# tvbgone.net
KiCad netlist of a schematic drawn in EAGLE
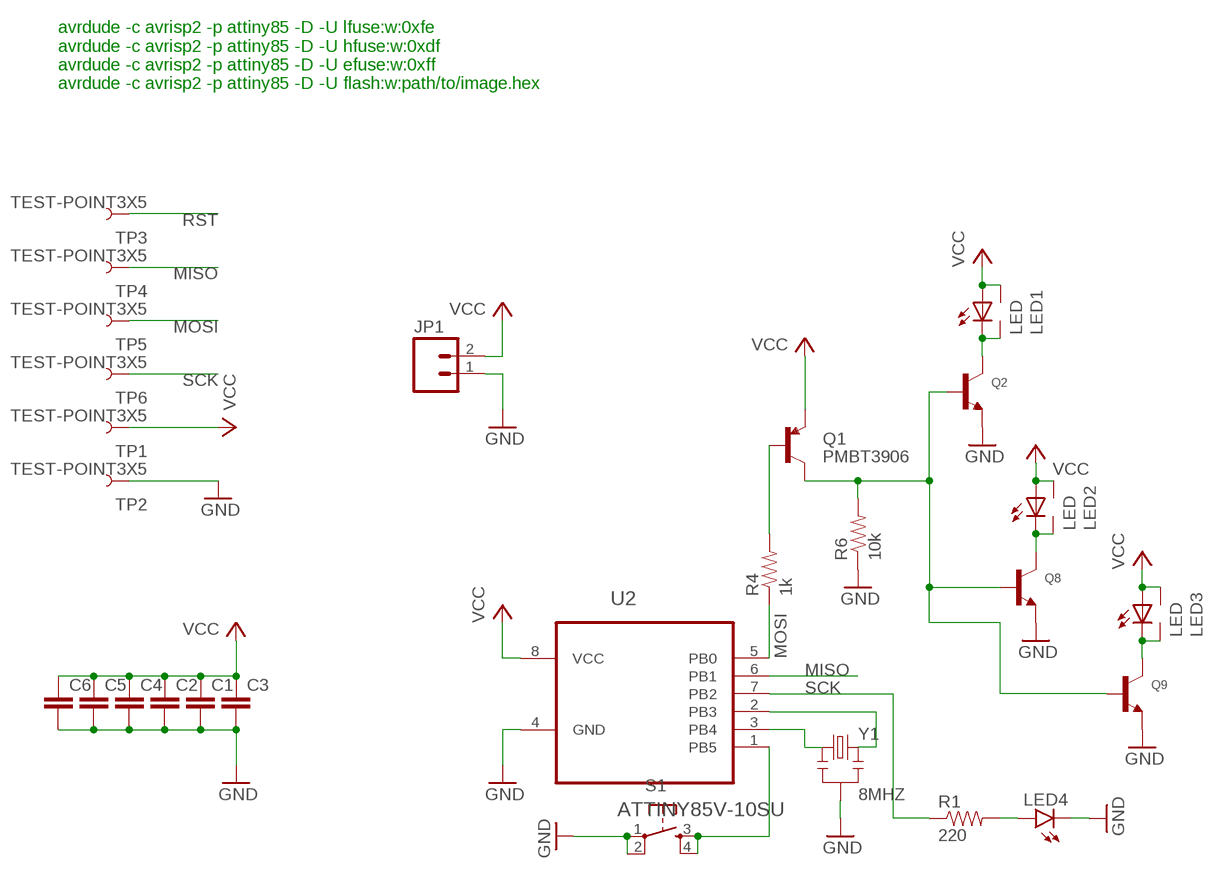
[diagram p0: schematic, sheet 1]

(export (version "E")
  (design (tool "Eeschema 10.0.6"))
  (components
    (comp (ref "C1")
      (value "CAP0603-CAP")
      (footprint "eagle-import:0603-CAP")
      (libsource (lib "eagle-import") (part "CAP0603-CAP"))
    )
    (comp (ref "C2")
      (value "CAP0603-CAP")
      (footprint "eagle-import:0603-CAP")
      (libsource (lib "eagle-import") (part "CAP0603-CAP"))
    )
    (comp (ref "C3")
      (value "CAP0603-CAP")
      (footprint "eagle-import:0603-CAP")
      (libsource (lib "eagle-import") (part "CAP0603-CAP"))
    )
    (comp (ref "C4")
      (value "CAP0603-CAP")
      (footprint "eagle-import:0603-CAP")
      (libsource (lib "eagle-import") (part "CAP0603-CAP"))
    )
    (comp (ref "C5")
      (value "CAP0603-CAP")
      (footprint "eagle-import:0603-CAP")
      (libsource (lib "eagle-import") (part "CAP0603-CAP"))
    )
    (comp (ref "C6")
      (value "CAP0603-CAP")
      (footprint "eagle-import:0603-CAP")
      (libsource (lib "eagle-import") (part "CAP0603-CAP"))
    )
    (comp (ref "JP1")
      (value "M02LOCK")
      (footprint "eagle-import:1X02_LOCK")
      (libsource (lib "eagle-import") (part "M02LOCK"))
    )
    (comp (ref "LED1")
      (value "LED")
      (footprint "eagle-import:5MM-SIDE")
      (libsource (lib "eagle-import") (part "LED"))
    )
    (comp (ref "LED2")
      (value "LED")
      (footprint "eagle-import:5MM-SIDE")
      (libsource (lib "eagle-import") (part "LED"))
    )
    (comp (ref "LED3")
      (value "LED")
      (footprint "eagle-import:5MM-SIDE")
      (libsource (lib "eagle-import") (part "LED"))
    )
    (comp (ref "LED4")
      (value "LED0603")
      (footprint "eagle-import:LED-0603")
      (libsource (lib "eagle-import") (part "LED0603"))
    )
    (comp (ref "Q1")
      (value "PMBT3906")
      (footprint "eagle-import:SOT23-3")
      (libsource (lib "eagle-import") (part "TRANSISTOR_PNPPMBT3906"))
    )
    (comp (ref "Q2")
      (value "TRANSISTOR_NPN")
      (footprint "eagle-import:SOT-23-R")
      (libsource (lib "eagle-import") (part "TRANSISTOR_NPN"))
    )
    (comp (ref "Q8")
      (value "TRANSISTOR_NPN")
      (footprint "eagle-import:SOT-23-R")
      (libsource (lib "eagle-import") (part "TRANSISTOR_NPN"))
    )
    (comp (ref "Q9")
      (value "TRANSISTOR_NPN")
      (footprint "eagle-import:SOT-23-R")
      (libsource (lib "eagle-import") (part "TRANSISTOR_NPN"))
    )
    (comp (ref "R1")
      (value "220")
      (footprint "eagle-import:0603-RES")
      (libsource (lib "eagle-import") (part "RESISTOR0603"))
    )
    (comp (ref "R4")
      (value "1k")
      (footprint "eagle-import:0603-RES")
      (libsource (lib "eagle-import") (part "RESISTOR0603"))
    )
    (comp (ref "R6")
      (value "10k")
      (footprint "eagle-import:0603-RES")
      (libsource (lib "eagle-import") (part "RESISTOR0603"))
    )
    (comp (ref "S1")
      (value "TAC_SWITCHSMD")
      (footprint "eagle-import:TACTILE-SWITCH-SMD")
      (libsource (lib "eagle-import") (part "TAC_SWITCHSMD"))
    )
    (comp (ref "TP1")
      (value "TEST-POINT3X5")
      (footprint "eagle-import:PAD.03X.05")
      (libsource (lib "eagle-import") (part "TEST-POINT3X5"))
    )
    (comp (ref "TP2")
      (value "TEST-POINT3X5")
      (footprint "eagle-import:PAD.03X.05")
      (libsource (lib "eagle-import") (part "TEST-POINT3X5"))
    )
    (comp (ref "TP3")
      (value "TEST-POINT3X5")
      (footprint "eagle-import:PAD.03X.05")
      (libsource (lib "eagle-import") (part "TEST-POINT3X5"))
    )
    (comp (ref "TP4")
      (value "TEST-POINT3X5")
      (footprint "eagle-import:PAD.03X.05")
      (libsource (lib "eagle-import") (part "TEST-POINT3X5"))
    )
    (comp (ref "TP5")
      (value "TEST-POINT3X5")
      (footprint "eagle-import:PAD.03X.05")
      (libsource (lib "eagle-import") (part "TEST-POINT3X5"))
    )
    (comp (ref "TP6")
      (value "TEST-POINT3X5")
      (footprint "eagle-import:PAD.03X.05")
      (libsource (lib "eagle-import") (part "TEST-POINT3X5"))
    )
    (comp (ref "U2")
      (value "ATTINY85V-10SU")
      (footprint "eagle-import:SOIC127P798X216-8N")
      (libsource (lib "eagle-import") (part "ATTINY85V-10SU"))
    )
    (comp (ref "Y1")
      (value "8MHZ")
      (footprint "eagle-import:RESONATOR-SMD")
      (libsource (lib "eagle-import") (part "RESONATOR8MHZ"))
    )
  )
  (nets
    (net (code "1") (name "/MISO") (class "Default")
      (node (ref "TP4") (pin "P$1") (pinfunction "1_P$1") (pintype "bidirectional"))
      (node (ref "U2") (pin "6") (pinfunction "PB1_6") (pintype "bidirectional"))
    )
    (net (code "2") (name "/MOSI") (class "Default")
      (node (ref "R4") (pin "1") (pinfunction "1_1") (pintype "passive"))
      (node (ref "TP5") (pin "P$1") (pinfunction "1_P$1") (pintype "bidirectional"))
      (node (ref "U2") (pin "5") (pinfunction "PB0_5") (pintype "bidirectional"))
    )
    (net (code "3") (name "/RST") (class "Default")
      (node (ref "S1") (pin "3") (pinfunction "3_3") (pintype "passive"))
      (node (ref "S1") (pin "4") (pinfunction "4_4") (pintype "passive"))
      (node (ref "TP3") (pin "P$1") (pinfunction "1_P$1") (pintype "bidirectional"))
      (node (ref "U2") (pin "1") (pinfunction "PB5_1") (pintype "bidirectional"))
    )
    (net (code "4") (name "/SCK") (class "Default")
      (node (ref "R1") (pin "1") (pinfunction "1_1") (pintype "passive"))
      (node (ref "TP6") (pin "P$1") (pinfunction "1_P$1") (pintype "bidirectional"))
      (node (ref "U2") (pin "7") (pinfunction "PB2_7") (pintype "bidirectional"))
    )
    (net (code "5") (name "GND") (class "Default")
      (node (ref "C1") (pin "2") (pinfunction "2_2") (pintype "passive"))
      (node (ref "C2") (pin "2") (pinfunction "2_2") (pintype "passive"))
      (node (ref "C3") (pin "2") (pinfunction "2_2") (pintype "passive"))
      (node (ref "C4") (pin "2") (pinfunction "2_2") (pintype "passive"))
      (node (ref "C5") (pin "2") (pinfunction "2_2") (pintype "passive"))
      (node (ref "C6") (pin "2") (pinfunction "2_2") (pintype "passive"))
      (node (ref "JP1") (pin "1") (pinfunction "1_1") (pintype "passive"))
      (node (ref "LED4") (pin "C") (pinfunction "C_C") (pintype "passive"))
      (node (ref "Q2") (pin "3-EMITTER") (pinfunction "E_3-EMITTER") (pintype "passive"))
      (node (ref "Q8") (pin "3-EMITTER") (pinfunction "E_3-EMITTER") (pintype "passive"))
      (node (ref "Q9") (pin "3-EMITTER") (pinfunction "E_3-EMITTER") (pintype "passive"))
      (node (ref "R6") (pin "1") (pinfunction "1_1") (pintype "passive"))
      (node (ref "S1") (pin "1") (pinfunction "1_1") (pintype "passive"))
      (node (ref "S1") (pin "2") (pinfunction "2_2") (pintype "passive"))
      (node (ref "TP2") (pin "P$1") (pinfunction "1_P$1") (pintype "bidirectional"))
      (node (ref "U2") (pin "4") (pinfunction "GND_4") (pintype "passive"))
      (node (ref "Y1") (pin "2") (pinfunction "2_2") (pintype "passive"))
    )
    (net (code "6") (name "Net-(LED1-C)") (class "Default")
      (node (ref "LED1") (pin "K") (pinfunction "C_K") (pintype "passive"))
      (node (ref "LED1") (pin "K2") (pinfunction "C1_K2") (pintype "passive"))
      (node (ref "Q2") (pin "2-COLLECTOR") (pinfunction "C_2-COLLECTOR") (pintype "passive"))
    )
    (net (code "7") (name "Net-(LED2-C)") (class "Default")
      (node (ref "LED2") (pin "K") (pinfunction "C_K") (pintype "passive"))
      (node (ref "LED2") (pin "K2") (pinfunction "C1_K2") (pintype "passive"))
      (node (ref "Q8") (pin "2-COLLECTOR") (pinfunction "C_2-COLLECTOR") (pintype "passive"))
    )
    (net (code "8") (name "Net-(LED3-C)") (class "Default")
      (node (ref "LED3") (pin "K") (pinfunction "C_K") (pintype "passive"))
      (node (ref "LED3") (pin "K2") (pinfunction "C1_K2") (pintype "passive"))
      (node (ref "Q9") (pin "2-COLLECTOR") (pinfunction "C_2-COLLECTOR") (pintype "passive"))
    )
    (net (code "9") (name "Net-(LED4-PadA)") (class "Default")
      (node (ref "LED4") (pin "A") (pinfunction "A_A") (pintype "passive"))
      (node (ref "R1") (pin "2") (pinfunction "2_2") (pintype "passive"))
    )
    (net (code "10") (name "Net-(Q1-B)") (class "Default")
      (node (ref "Q1") (pin "1") (pinfunction "B_1") (pintype "passive"))
      (node (ref "R4") (pin "2") (pinfunction "2_2") (pintype "passive"))
    )
    (net (code "11") (name "Net-(Q1-C)") (class "Default")
      (node (ref "Q1") (pin "3") (pinfunction "C_3") (pintype "passive"))
      (node (ref "Q2") (pin "1-BASE") (pinfunction "B_1-BASE") (pintype "passive"))
      (node (ref "Q8") (pin "1-BASE") (pinfunction "B_1-BASE") (pintype "passive"))
      (node (ref "Q9") (pin "1-BASE") (pinfunction "B_1-BASE") (pintype "passive"))
      (node (ref "R6") (pin "2") (pinfunction "2_2") (pintype "passive"))
    )
    (net (code "12") (name "Net-(U2-PB3)") (class "Default")
      (node (ref "U2") (pin "2") (pinfunction "PB3_2") (pintype "bidirectional"))
      (node (ref "Y1") (pin "3") (pinfunction "3_3") (pintype "passive"))
    )
    (net (code "13") (name "Net-(U2-PB4)") (class "Default")
      (node (ref "U2") (pin "3") (pinfunction "PB4_3") (pintype "bidirectional"))
      (node (ref "Y1") (pin "1") (pinfunction "1_1") (pintype "passive"))
    )
    (net (code "14") (name "VCC") (class "Default")
      (node (ref "C1") (pin "1") (pinfunction "1_1") (pintype "passive"))
      (node (ref "C2") (pin "1") (pinfunction "1_1") (pintype "passive"))
      (node (ref "C3") (pin "1") (pinfunction "1_1") (pintype "passive"))
      (node (ref "C4") (pin "1") (pinfunction "1_1") (pintype "passive"))
      (node (ref "C5") (pin "1") (pinfunction "1_1") (pintype "passive"))
      (node (ref "C6") (pin "1") (pinfunction "1_1") (pintype "passive"))
      (node (ref "JP1") (pin "2") (pinfunction "2_2") (pintype "passive"))
      (node (ref "LED1") (pin "A") (pinfunction "A_A") (pintype "passive"))
      (node (ref "LED1") (pin "A2") (pinfunction "A1_A2") (pintype "passive"))
      (node (ref "LED2") (pin "A") (pinfunction "A_A") (pintype "passive"))
      (node (ref "LED2") (pin "A2") (pinfunction "A1_A2") (pintype "passive"))
      (node (ref "LED3") (pin "A") (pinfunction "A_A") (pintype "passive"))
      (node (ref "LED3") (pin "A2") (pinfunction "A1_A2") (pintype "passive"))
      (node (ref "Q1") (pin "2") (pinfunction "E_2") (pintype "passive"))
      (node (ref "TP1") (pin "P$1") (pinfunction "1_P$1") (pintype "bidirectional"))
      (node (ref "U2") (pin "8") (pinfunction "VCC_8") (pintype "power_in"))
    )
  )
)
